# sch.net
KiCad netlist of a schematic drawn in Altium Designer
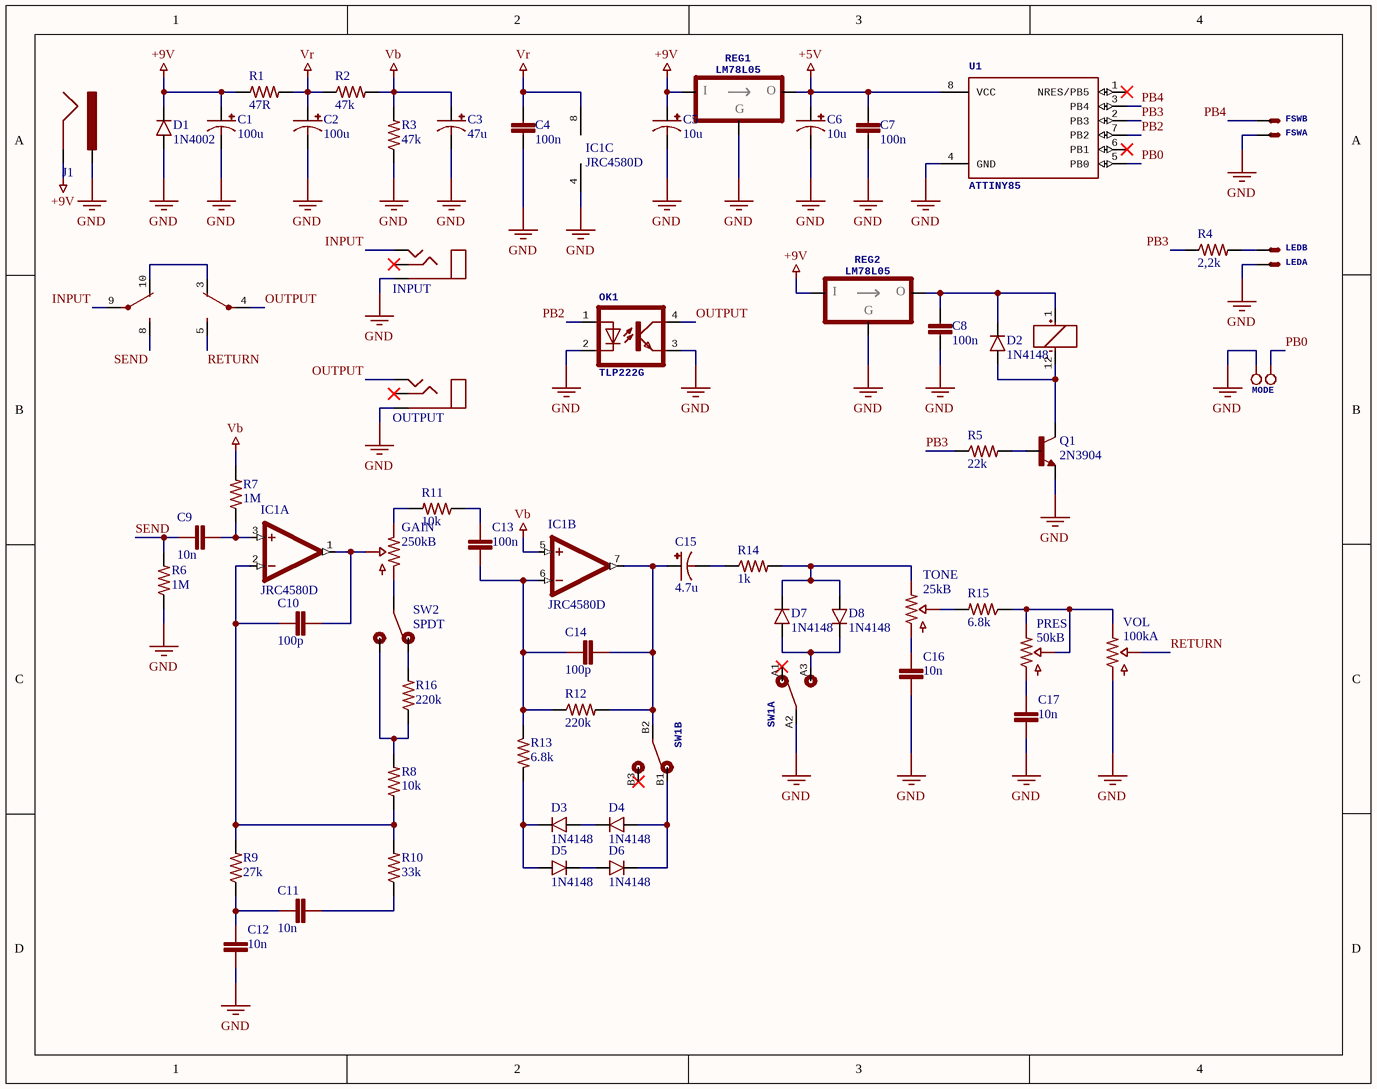
[diagram p0: sch.SchDoc]

(export (version "E")
  (design (tool "Eeschema 10.0.6"))
  (components
    (comp (ref "C1")
      (value "100u")
      (footprint "ELEC_063_025")
      (description "100u 25V electrolytic capacitor")
      (libsource (lib "Pedals") (part "ELEC_100u_25V"))
    )
    (comp (ref "C2")
      (value "100u")
      (footprint "ELEC_063_025")
      (description "100u 25V electrolytic capacitor")
      (libsource (lib "Pedals") (part "ELEC_100u_25V"))
    )
    (comp (ref "C3")
      (value "47u")
      (footprint "ELEC_050_020")
      (description "47u 25V electrolytic capacitor")
      (libsource (lib "Pedals") (part "ELEC_47u_25V"))
    )
    (comp (ref "C4")
      (value "100n")
      (footprint "CER_050")
      (description "100n MLCC X7R radial capacitor")
      (libsource (lib "") (part "CER_100n_1"))
    )
    (comp (ref "C5")
      (value "10u")
      (footprint "ELEC_040_020")
      (description "10u 50V electrolytic capacitor")
      (libsource (lib "Pedals") (part "ELEC_10u_50V"))
    )
    (comp (ref "C6")
      (value "10u")
      (footprint "ELEC_040_020")
      (description "10u 50V electrolytic capacitor")
      (libsource (lib "Pedals") (part "ELEC_10u_50V"))
    )
    (comp (ref "C7")
      (value "100n")
      (footprint "CER_050")
      (description "100n MLCC X7R radial capacitor")
      (libsource (lib "Pedals") (part "CER_100n"))
    )
    (comp (ref "C8")
      (value "100n")
      (footprint "CER_050")
      (description "100n MLCC X7R radial capacitor")
      (libsource (lib "") (part "CER_100n_1"))
    )
    (comp (ref "C9")
      (value "10n")
      (footprint "FILMBOX_SMALL")
      (description "10n 100V polyester film box capacitor")
      (libsource (lib "") (part "FILMBOX_10n_1"))
    )
    (comp (ref "C10")
      (value "100p")
      (footprint "CER_050")
      (description "100p MLCC X7R radial capacitor")
      (libsource (lib "Pedals") (part "CER_100p"))
    )
    (comp (ref "C11")
      (value "10n")
      (footprint "FILMBOX_SMALL")
      (description "10n 100V polyester film box capacitor")
      (libsource (lib "") (part "FILMBOX_10n_1"))
    )
    (comp (ref "C12")
      (value "10n")
      (footprint "FILMBOX_SMALL")
      (description "10n 100V polyester film box capacitor")
      (libsource (lib "") (part "FILMBOX_10n_2"))
    )
    (comp (ref "C13")
      (value "100n")
      (footprint "FILMBOX_SMALL")
      (description "100n 100V polyester film box capacitor")
      (libsource (lib "Pedals") (part "FILMBOX_100n"))
    )
    (comp (ref "C14")
      (value "100p")
      (footprint "CER_050")
      (description "100p MLCC X7R radial capacitor")
      (libsource (lib "Pedals") (part "CER_100p"))
    )
    (comp (ref "C15")
      (value "4.7u")
      (footprint "ELEC_LESR_050_020")
      (description "4.7u 50V Low ESR ectrolytic capacitor")
      (libsource (lib "Pedals") (part "ELEC_LESR_4.7u_50V"))
    )
    (comp (ref "C16")
      (value "10n")
      (footprint "FILMBOX_SMALL")
      (description "10n 100V polyester film box capacitor")
      (libsource (lib "") (part "FILMBOX_10n_2"))
    )
    (comp (ref "C17")
      (value "10n")
      (footprint "FILMBOX_SMALL")
      (description "10n 100V polyester film box capacitor")
      (libsource (lib "Pedals") (part "FILMBOX_10n"))
    )
    (comp (ref "D1") (value "1N4002") (footprint "DO41_2") (libsource (lib "Pedals") (part "1N4002")))
    (comp (ref "D2") (value "1N4148") (footprint "DO35_2") (libsource (lib "Pedals") (part "1N4148")))
    (comp (ref "D3") (value "1N4148") (footprint "DO35_2") (libsource (lib "Pedals") (part "1N4148")))
    (comp (ref "D4") (value "1N4148") (footprint "DO35_2") (libsource (lib "Pedals") (part "1N4148")))
    (comp (ref "D5") (value "1N4148") (footprint "DO35_2") (libsource (lib "Pedals") (part "1N4148")))
    (comp (ref "D6") (value "1N4148") (footprint "DO35_2") (libsource (lib "Pedals") (part "1N4148")))
    (comp (ref "D7") (value "1N4148") (footprint "DO35_2") (libsource (lib "Pedals") (part "1N4148")))
    (comp (ref "D8") (value "1N4148") (footprint "DO35_2") (libsource (lib "Pedals") (part "1N4148")))
    (comp (ref "FSW")
      (value "~")
      (footprint "JST-XH-02")
      (description "2 Pins male XH header")
      (libsource (lib "Pedals") (part "JST-XH-02"))
    )
    (comp (ref "GAIN")
      (value "250kB")
      (footprint "ALPHA_16mm_BOTTOM")
      (description "250k Lin potentiometer round shaft")
      (libsource (lib "Pedals") (part "250kB_ALPHA_16mm"))
    )
    (comp (ref "IC1") (value "JRC4580D") (footprint "DIL8") (libsource (lib "Pedals") (part "JRC4580D")))
    (comp (ref "INPUT")
      (value "~")
      (footprint "STEREO")
      (description "6.35mm stereo insulated socket jack PCB mounted")
      (libsource (lib "Pedals") (part "STEREO"))
    )
    (comp (ref "J1")
      (value "DC_JACK")
      (footprint "DC_JACK")
      (description "DC Power jack 2.1mm barrel")
      (libsource (lib "Pedals") (part "DC_JACK"))
    )
    (comp (ref "K1")
      (value "~")
      (footprint "NA5")
      (description "NA5W-K")
      (libsource (lib "Pedals") (part "NA5W-K"))
    )
    (comp (ref "LED")
      (value "~")
      (footprint "JST-XH-02")
      (description "2 Pins male XH header")
      (libsource (lib "Pedals") (part "JST-XH-02"))
    )
    (comp (ref "MODE")
      (value "HEADER_2PINS")
      (footprint "HEADER_2PINS")
      (description "2 Pins male header")
      (libsource (lib "Pedals") (part "HEADER_2PINS"))
    )
    (comp (ref "OK1") (value "TLP222G") (footprint "DIL4") (libsource (lib "Pedals") (part "TLP222G")))
    (comp (ref "OUTPUT")
      (value "~")
      (footprint "STEREO")
      (description "6.35mm stereo insulated socket jack PCB mounted")
      (libsource (lib "Pedals") (part "STEREO"))
    )
    (comp (ref "PRES")
      (value "50kB")
      (footprint "BOURNS_3296W")
      (description "50k Lin 3296W trimmer")
      (libsource (lib "Pedals") (part "50kB_TRIM_3296W"))
    )
    (comp (ref "Q1") (value "2N3904") (footprint "TO92") (libsource (lib "Pedals") (part "2N3904")))
    (comp (ref "R1")
      (value "47R")
      (footprint "R_3_47R_025W")
      (description "47R metal film 1/4W Resistor")
      (libsource (lib "Pedals") (part "R_3_47R_025W"))
    )
    (comp (ref "R2")
      (value "47k")
      (footprint "R_3_47k_025W")
      (description "47k metal film 1/4W Resistor")
      (libsource (lib "Pedals") (part "R_3_47k_025W"))
    )
    (comp (ref "R3")
      (value "47k")
      (footprint "R_3_47k_025W")
      (description "47k metal film 1/4W Resistor")
      (libsource (lib "Pedals") (part "R_3_47k_025W"))
    )
    (comp (ref "R4")
      (value "2,2k")
      (footprint "R_3_2,2k_025W")
      (libsource (lib "Pedals") (part "R_3_2,2k_025W"))
    )
    (comp (ref "R5")
      (value "22k")
      (footprint "R_3_22k_025W")
      (description "22k metal film 1/4W Resistor")
      (libsource (lib "Pedals") (part "R_3_22k_025W"))
    )
    (comp (ref "R6")
      (value "1M")
      (footprint "R_3_1M_025W")
      (description "1M metal film 1/4W Resistor")
      (libsource (lib "Pedals") (part "R_3_1M_025W"))
    )
    (comp (ref "R7")
      (value "1M")
      (footprint "R_3_1M_025W")
      (description "1M metal film 1/4W Resistor")
      (libsource (lib "Pedals") (part "R_3_1M_025W"))
    )
    (comp (ref "R8")
      (value "10k")
      (footprint "R_3_10k_025W")
      (description "10k metal film 1/4W Resistor")
      (libsource (lib "Pedals") (part "R_3_10k_025W"))
    )
    (comp (ref "R9")
      (value "27k")
      (footprint "R_3_27k_025W")
      (description "27k metal film 1/4W Resistor")
      (libsource (lib "Pedals") (part "R_3_27k_025W"))
    )
    (comp (ref "R10")
      (value "33k")
      (footprint "R_3_33k_025W")
      (description "33k metal film 1/4W Resistor")
      (libsource (lib "Pedals") (part "R_3_33k_025W"))
    )
    (comp (ref "R11")
      (value "10k")
      (footprint "R_3_10k_025W")
      (description "10k metal film 1/4W Resistor")
      (libsource (lib "Pedals") (part "R_3_10k_025W"))
    )
    (comp (ref "R12")
      (value "220k")
      (footprint "R_3_220k_025W")
      (description "220k metal film 1/4W Resistor")
      (libsource (lib "Pedals") (part "R_3_220k_025W"))
    )
    (comp (ref "R13")
      (value "6.8k")
      (footprint "R_3_6.8k_025W")
      (description "6.8k metal film 1/4W Resistor")
      (libsource (lib "Pedals") (part "R_3_6.8k_025W"))
    )
    (comp (ref "R14")
      (value "1k")
      (footprint "R_3_1k_025W")
      (description "1k metal film 1/4W Resistor")
      (libsource (lib "Pedals") (part "R_3_1k_025W"))
    )
    (comp (ref "R15")
      (value "6.8k")
      (footprint "R_3_6.8k_025W")
      (description "6.8k metal film 1/4W Resistor")
      (libsource (lib "Pedals") (part "R_3_6.8k_025W"))
    )
    (comp (ref "R16")
      (value "220k")
      (footprint "R_3_220k_025W")
      (description "220k metal film 1/4W Resistor")
      (libsource (lib "Pedals") (part "R_3_220k_025W"))
    )
    (comp (ref "REG1")
      (value "LM78L05")
      (footprint "TO92")
      (description "78L05")
      (libsource (lib "Pedals") (part "LM78L05"))
    )
    (comp (ref "REG2")
      (value "LM78L05")
      (footprint "TO92")
      (description "78L05")
      (libsource (lib "Pedals") (part "LM78L05"))
    )
    (comp (ref "SW1")
      (value "DPDT")
      (footprint "DPDT")
      (description "DPDT toggle switch ON/OFF/ON")
      (libsource (lib "") (part "DPDT_ON-OFF-ON_1"))
    )
    (comp (ref "SW2")
      (value "SPDT")
      (footprint "SPDT")
      (description "SPDT toggle switch ON/ON")
      (libsource (lib "Pedals") (part "SPDT_ON-ON"))
    )
    (comp (ref "TONE")
      (value "25kB")
      (footprint "ALPHA_16mm_BOTTOM")
      (description "25k Lin potentiometer round shaft")
      (libsource (lib "Pedals") (part "25kB_ALPHA_16mm"))
    )
    (comp (ref "U1")
      (value "ATTINY85")
      (footprint "DIP8")
      (description "ATTINY85-20PU")
      (libsource (lib "Pedals") (part "ATTINY85"))
    )
    (comp (ref "VOL")
      (value "100kA")
      (footprint "ALPHA_16mm_BOTTOM")
      (description "100k Log potentiometer round shaft")
      (libsource (lib "Pedals") (part "100kA_ALPHA_16mm"))
    )
  )
  (nets
    (net (code "1") (name "+5V") (class "Default")
      (node (ref "C6") (pin "+") (pinfunction "+_+") (pintype "passive"))
      (node (ref "C7") (pin "2") (pinfunction "2_2") (pintype "passive"))
      (node (ref "REG1") (pin "3") (pinfunction "VO_3") (pintype "power_in"))
      (node (ref "U1") (pin "8") (pinfunction "VCC_8") (pintype "power_in"))
    )
    (net (code "2") (name "+9V") (class "Default")
      (node (ref "C1") (pin "+") (pinfunction "+_+") (pintype "passive"))
      (node (ref "C5") (pin "+") (pinfunction "+_+") (pintype "passive"))
      (node (ref "D1") (pin "C") (pinfunction "C_C") (pintype "passive"))
      (node (ref "J1") (pin "GND") (pinfunction "GND_GND") (pintype "passive"))
      (node (ref "R1") (pin "1") (pinfunction "1_1") (pintype "passive"))
      (node (ref "REG1") (pin "1") (pinfunction "VI_1") (pintype "power_in"))
      (node (ref "REG2") (pin "1") (pinfunction "VI_1") (pintype "power_in"))
    )
    (net (code "3") (name "/INPUT") (class "Default")
      (node (ref "INPUT") (pin "T") (pinfunction "T_T") (pintype "passive"))
      (node (ref "K1") (pin "9") (pinfunction "P_9") (pintype "passive"))
    )
    (net (code "4") (name "/OUTPUT") (class "Default")
      (node (ref "K1") (pin "4") (pinfunction "P_4") (pintype "passive"))
      (node (ref "OK1") (pin "4") (pinfunction "COL_4") (pintype "passive"))
      (node (ref "OUTPUT") (pin "T") (pinfunction "T_T") (pintype "passive"))
    )
    (net (code "5") (name "/PB0") (class "Default")
      (node (ref "MODE") (pin "2") (pinfunction "2_2") (pintype "passive"))
      (node (ref "U1") (pin "5") (pinfunction "PB0_5") (pintype "bidirectional"))
    )
    (net (code "6") (name "/PB2") (class "Default")
      (node (ref "OK1") (pin "1") (pinfunction "A_1") (pintype "passive"))
      (node (ref "U1") (pin "7") (pinfunction "PB2_7") (pintype "bidirectional"))
    )
    (net (code "7") (name "/PB3") (class "Default")
      (node (ref "R4") (pin "1") (pinfunction "1_1") (pintype "passive"))
      (node (ref "R5") (pin "1") (pinfunction "1_1") (pintype "passive"))
      (node (ref "U1") (pin "2") (pinfunction "PB3_2") (pintype "bidirectional"))
    )
    (net (code "8") (name "/PB4") (class "Default")
      (node (ref "FSW") (pin "1") (pinfunction "S_1") (pintype "passive"))
      (node (ref "U1") (pin "3") (pinfunction "PB4_3") (pintype "bidirectional"))
    )
    (net (code "9") (name "/RETURN") (class "Default")
      (node (ref "K1") (pin "5") (pinfunction "S_5") (pintype "passive"))
      (node (ref "VOL") (pin "2") (pinfunction "2_2") (pintype "passive"))
    )
    (net (code "10") (name "/SEND") (class "Default")
      (node (ref "C9") (pin "2") (pinfunction "2_2") (pintype "passive"))
      (node (ref "K1") (pin "8") (pinfunction "S_8") (pintype "passive"))
      (node (ref "R6") (pin "2") (pinfunction "2_2") (pintype "passive"))
    )
    (net (code "11") (name "GND") (class "Default")
      (node (ref "C1") (pin "-") (pinfunction "-_-") (pintype "passive"))
      (node (ref "C12") (pin "2") (pinfunction "2_2") (pintype "passive"))
      (node (ref "C16") (pin "2") (pinfunction "2_2") (pintype "passive"))
      (node (ref "C17") (pin "1") (pinfunction "1_1") (pintype "passive"))
      (node (ref "C2") (pin "-") (pinfunction "-_-") (pintype "passive"))
      (node (ref "C3") (pin "-") (pinfunction "-_-") (pintype "passive"))
      (node (ref "C4") (pin "2") (pinfunction "2_2") (pintype "passive"))
      (node (ref "C5") (pin "-") (pinfunction "-_-") (pintype "passive"))
      (node (ref "C6") (pin "-") (pinfunction "-_-") (pintype "passive"))
      (node (ref "C7") (pin "1") (pinfunction "1_1") (pintype "passive"))
      (node (ref "C8") (pin "2") (pinfunction "2_2") (pintype "passive"))
      (node (ref "D1") (pin "A") (pinfunction "A_A") (pintype "passive"))
      (node (ref "FSW") (pin "2") (pinfunction "S_2") (pintype "passive"))
      (node (ref "IC1") (pin "4") (pinfunction "V-_4") (pintype "power_in"))
      (node (ref "INPUT") (pin "S") (pinfunction "S_S") (pintype "passive"))
      (node (ref "J1") (pin "PWR") (pinfunction "PWR_PWR") (pintype "passive"))
      (node (ref "LED") (pin "2") (pinfunction "S_2") (pintype "passive"))
      (node (ref "MODE") (pin "1") (pinfunction "1_1") (pintype "passive"))
      (node (ref "OK1") (pin "2") (pinfunction "C_2") (pintype "passive"))
      (node (ref "OK1") (pin "3") (pinfunction "EMIT_3") (pintype "passive"))
      (node (ref "OUTPUT") (pin "S") (pinfunction "S_S") (pintype "passive"))
      (node (ref "Q1") (pin "3") (pinfunction "E_3") (pintype "passive"))
      (node (ref "R3") (pin "1") (pinfunction "1_1") (pintype "passive"))
      (node (ref "R6") (pin "1") (pinfunction "1_1") (pintype "passive"))
      (node (ref "REG1") (pin "2") (pinfunction "GND_2") (pintype "power_in"))
      (node (ref "REG2") (pin "2") (pinfunction "GND_2") (pintype "power_in"))
      (node (ref "SW1") (pin "A2") (pinfunction "2_A2") (pintype "passive"))
      (node (ref "U1") (pin "4") (pinfunction "GND_4") (pintype "power_in"))
      (node (ref "VOL") (pin "1") (pinfunction "1_1") (pintype "passive"))
    )
    (net (code "12") (name "Net-(C11-Pad1)") (class "Default")
      (node (ref "C11") (pin "1") (pinfunction "1_1") (pintype "passive"))
      (node (ref "R10") (pin "1") (pinfunction "1_1") (pintype "passive"))
    )
    (net (code "13") (name "Net-(C11-Pad2)") (class "Default")
      (node (ref "C11") (pin "2") (pinfunction "2_2") (pintype "passive"))
      (node (ref "C12") (pin "1") (pinfunction "1_1") (pintype "passive"))
      (node (ref "R9") (pin "1") (pinfunction "1_1") (pintype "passive"))
    )
    (net (code "14") (name "Net-(C13-Pad1)") (class "Default")
      (node (ref "C13") (pin "1") (pinfunction "1_1") (pintype "passive"))
      (node (ref "R11") (pin "1") (pinfunction "1_1") (pintype "passive"))
    )
    (net (code "15") (name "Net-(C15-Pad-)") (class "Default")
      (node (ref "C15") (pin "-") (pinfunction "-_-") (pintype "passive"))
      (node (ref "R14") (pin "1") (pinfunction "1_1") (pintype "passive"))
    )
    (net (code "16") (name "Net-(C16-Pad1)") (class "Default")
      (node (ref "C16") (pin "1") (pinfunction "1_1") (pintype "passive"))
      (node (ref "TONE") (pin "1") (pinfunction "1_1") (pintype "passive"))
    )
    (net (code "17") (name "Net-(C17-Pad2)") (class "Default")
      (node (ref "C17") (pin "2") (pinfunction "2_2") (pintype "passive"))
      (node (ref "PRES") (pin "1") (pinfunction "1_1") (pintype "passive"))
    )
    (net (code "18") (name "Net-(D3-PadA)") (class "Default")
      (node (ref "D3") (pin "A") (pinfunction "A_A") (pintype "passive"))
      (node (ref "D4") (pin "C") (pinfunction "C_C") (pintype "passive"))
    )
    (net (code "19") (name "Net-(D3-PadC)") (class "Default")
      (node (ref "D3") (pin "C") (pinfunction "C_C") (pintype "passive"))
      (node (ref "D5") (pin "A") (pinfunction "A_A") (pintype "passive"))
      (node (ref "R13") (pin "2") (pinfunction "2_2") (pintype "passive"))
    )
    (net (code "20") (name "Net-(D5-PadC)") (class "Default")
      (node (ref "D5") (pin "C") (pinfunction "C_C") (pintype "passive"))
      (node (ref "D6") (pin "A") (pinfunction "A_A") (pintype "passive"))
    )
    (net (code "21") (name "Net-(D7-PadC)") (class "Default")
      (node (ref "D7") (pin "C") (pinfunction "C_C") (pintype "passive"))
      (node (ref "D8") (pin "A") (pinfunction "A_A") (pintype "passive"))
      (node (ref "R14") (pin "2") (pinfunction "2_2") (pintype "passive"))
      (node (ref "TONE") (pin "3") (pinfunction "3_3") (pintype "passive"))
    )
    (net (code "22") (name "Net-(GAIN-Pad3)") (class "Default")
      (node (ref "GAIN") (pin "3") (pinfunction "3_3") (pintype "passive"))
      (node (ref "R11") (pin "2") (pinfunction "2_2") (pintype "passive"))
    )
    (net (code "23") (name "Net-(IC1A-+IN)") (class "Default")
      (node (ref "C9") (pin "1") (pinfunction "1_1") (pintype "passive"))
      (node (ref "IC1") (pin "3") (pinfunction "+IN_3") (pintype "input"))
      (node (ref "R7") (pin "1") (pinfunction "1_1") (pintype "passive"))
    )
    (net (code "24") (name "Net-(IC1A--IN)") (class "Default")
      (node (ref "C10") (pin "2") (pinfunction "2_2") (pintype "passive"))
      (node (ref "IC1") (pin "2") (pinfunction "-IN_2") (pintype "input"))
      (node (ref "R10") (pin "2") (pinfunction "2_2") (pintype "passive"))
      (node (ref "R8") (pin "1") (pinfunction "1_1") (pintype "passive"))
      (node (ref "R9") (pin "2") (pinfunction "2_2") (pintype "passive"))
    )
    (net (code "25") (name "Net-(IC1A-OUT)") (class "Default")
      (node (ref "C10") (pin "1") (pinfunction "1_1") (pintype "passive"))
      (node (ref "GAIN") (pin "2") (pinfunction "2_2") (pintype "passive"))
      (node (ref "IC1") (pin "1") (pinfunction "OUT_1") (pintype "output"))
    )
    (net (code "26") (name "Net-(IC1B--IN)") (class "Default")
      (node (ref "C13") (pin "2") (pinfunction "2_2") (pintype "passive"))
      (node (ref "C14") (pin "2") (pinfunction "2_2") (pintype "passive"))
      (node (ref "IC1") (pin "6") (pinfunction "-IN_6") (pintype "input"))
      (node (ref "R12") (pin "1") (pinfunction "1_1") (pintype "passive"))
      (node (ref "R13") (pin "1") (pinfunction "1_1") (pintype "passive"))
    )
    (net (code "27") (name "Net-(IC1B-OUT)") (class "Default")
      (node (ref "C14") (pin "1") (pinfunction "1_1") (pintype "passive"))
      (node (ref "C15") (pin "+") (pinfunction "+_+") (pintype "passive"))
      (node (ref "IC1") (pin "7") (pinfunction "OUT_7") (pintype "output"))
      (node (ref "R12") (pin "2") (pinfunction "2_2") (pintype "passive"))
      (node (ref "SW1") (pin "B2") (pinfunction "2_B2") (pintype "passive"))
    )
    (net (code "28") (name "Net-(K1A-+)") (class "Default")
      (node (ref "C8") (pin "1") (pinfunction "1_1") (pintype "passive"))
      (node (ref "D2") (pin "C") (pinfunction "C_C") (pintype "passive"))
      (node (ref "K1") (pin "1") (pinfunction "+_1") (pintype "passive"))
      (node (ref "REG2") (pin "3") (pinfunction "VO_3") (pintype "power_in"))
    )
    (net (code "29") (name "Net-(K1A--)") (class "Default")
      (node (ref "D2") (pin "A") (pinfunction "A_A") (pintype "passive"))
      (node (ref "K1") (pin "12") (pinfunction "-_12") (pintype "passive"))
      (node (ref "Q1") (pin "1") (pinfunction "C_1") (pintype "passive"))
    )
    (net (code "30") (name "Net-(K1B-O)") (class "Default")
      (node (ref "K1") (pin "10") (pinfunction "O_10") (pintype "passive"))
      (node (ref "K1") (pin "3") (pinfunction "O_3") (pintype "passive"))
    )
    (net (code "31") (name "Net-(LEDB-S)") (class "Default")
      (node (ref "LED") (pin "1") (pinfunction "S_1") (pintype "passive"))
      (node (ref "R4") (pin "2") (pinfunction "2_2") (pintype "passive"))
    )
    (net (code "32") (name "Net-(PRES-Pad2)") (class "Default")
      (node (ref "PRES") (pin "2") (pinfunction "2_2") (pintype "passive"))
      (node (ref "PRES") (pin "3") (pinfunction "3_3") (pintype "passive"))
      (node (ref "R15") (pin "1") (pinfunction "1_1") (pintype "passive"))
      (node (ref "VOL") (pin "3") (pinfunction "3_3") (pintype "passive"))
    )
    (net (code "33") (name "Net-(Q1-B)") (class "Default")
      (node (ref "Q1") (pin "2") (pinfunction "B_2") (pintype "passive"))
      (node (ref "R5") (pin "2") (pinfunction "2_2") (pintype "passive"))
    )
    (net (code "34") (name "Net-(R15-Pad2)") (class "Default")
      (node (ref "R15") (pin "2") (pinfunction "2_2") (pintype "passive"))
      (node (ref "TONE") (pin "2") (pinfunction "2_2") (pintype "passive"))
    )
    (net (code "35") (name "Net-(SW1A-3)") (class "Default")
      (node (ref "D7") (pin "A") (pinfunction "A_A") (pintype "passive"))
      (node (ref "D8") (pin "C") (pinfunction "C_C") (pintype "passive"))
      (node (ref "SW1") (pin "A3") (pinfunction "3_A3") (pintype "passive"))
    )
    (net (code "36") (name "Net-(SW1B-1)") (class "Default")
      (node (ref "D4") (pin "A") (pinfunction "A_A") (pintype "passive"))
      (node (ref "D6") (pin "C") (pinfunction "C_C") (pintype "passive"))
      (node (ref "SW1") (pin "B1") (pinfunction "1_B1") (pintype "passive"))
    )
    (net (code "37") (name "Net-(SW2-O)") (class "Default")
      (node (ref "R16") (pin "2") (pinfunction "2_2") (pintype "passive"))
      (node (ref "SW2") (pin "1") (pinfunction "O_1") (pintype "passive"))
    )
    (net (code "38") (name "Net-(SW2-P)") (class "Default")
      (node (ref "GAIN") (pin "1") (pinfunction "1_1") (pintype "passive"))
      (node (ref "SW2") (pin "2") (pinfunction "P_2") (pintype "passive"))
    )
    (net (code "39") (name "Net-(SW2-S)") (class "Default")
      (node (ref "R16") (pin "1") (pinfunction "1_1") (pintype "passive"))
      (node (ref "R8") (pin "2") (pinfunction "2_2") (pintype "passive"))
      (node (ref "SW2") (pin "3") (pinfunction "S_3") (pintype "passive"))
    )
    (net (code "40") (name "Vb") (class "Default")
      (node (ref "C3") (pin "+") (pinfunction "+_+") (pintype "passive"))
      (node (ref "IC1") (pin "5") (pinfunction "+IN_5") (pintype "input"))
      (node (ref "R2") (pin "2") (pinfunction "2_2") (pintype "passive"))
      (node (ref "R3") (pin "2") (pinfunction "2_2") (pintype "passive"))
      (node (ref "R7") (pin "2") (pinfunction "2_2") (pintype "passive"))
    )
    (net (code "41") (name "Vr") (class "Default")
      (node (ref "C2") (pin "+") (pinfunction "+_+") (pintype "passive"))
      (node (ref "C4") (pin "1") (pinfunction "1_1") (pintype "passive"))
      (node (ref "IC1") (pin "8") (pinfunction "V+_8") (pintype "power_in"))
      (node (ref "R1") (pin "2") (pinfunction "2_2") (pintype "passive"))
      (node (ref "R2") (pin "1") (pinfunction "1_1") (pintype "passive"))
    )
    (net (code "42") (name "unconnected-(INPUT-PadR)") (class "Default")
      (node (ref "INPUT") (pin "R") (pinfunction "R_R") (pintype "passive+no_connect"))
    )
    (net (code "43") (name "unconnected-(OUTPUT-PadR)") (class "Default")
      (node (ref "OUTPUT") (pin "R") (pinfunction "R_R") (pintype "passive+no_connect"))
    )
    (net (code "44") (name "unconnected-(SW1A-1-PadA1)") (class "Default")
      (node (ref "SW1") (pin "A1") (pinfunction "1_A1") (pintype "passive+no_connect"))
    )
    (net (code "45") (name "unconnected-(SW1B-3-PadB3)") (class "Default")
      (node (ref "SW1") (pin "B3") (pinfunction "3_B3") (pintype "passive+no_connect"))
    )
    (net (code "46") (name "unconnected-(U1-NRES{slash}PB5-Pad1)") (class "Default")
      (node (ref "U1") (pin "1") (pinfunction "NRES/PB5_1") (pintype "bidirectional+no_connect"))
    )
    (net (code "47") (name "unconnected-(U1-PB1-Pad6)") (class "Default")
      (node (ref "U1") (pin "6") (pinfunction "PB1_6") (pintype "bidirectional+no_connect"))
    )
  )
)
